# uMultimeter_PWR_Sch.net
KiCad netlist of a schematic drawn in Altium Designer
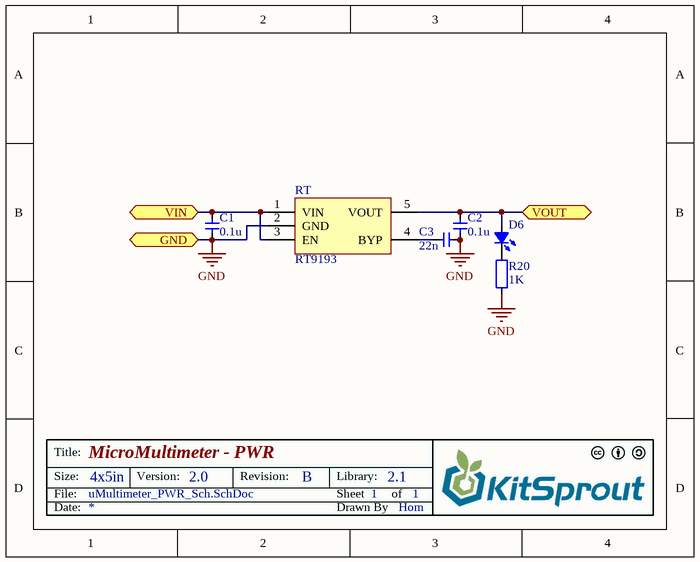
[diagram p0: uMultimeter_PWR_Sch.SchDoc]

(export (version "E")
  (design (tool "Eeschema 10.0.6"))
  (components
    (comp (ref "C1")
      (value "0.1u")
      (footprint "PCB_PassiveCap:CAP_0603")
      (description "Capacitor")
      (fields (field (name "Comment") "Cap_0603"))
      (libsource (lib "SCH_Passive") (part "Cap_0603"))
    )
    (comp (ref "C2")
      (value "0.1u")
      (footprint "PCB_PassiveCap:CAP_0603")
      (description "Capacitor")
      (fields (field (name "Comment") "Cap_0603"))
      (libsource (lib "SCH_Passive") (part "Cap_0603"))
    )
    (comp (ref "C3")
      (value "22n")
      (footprint "PCB_PassiveCap:CAP_0603")
      (description "Capacitor")
      (fields (field (name "Comment") "Cap_0603"))
      (libsource (lib "SCH_Passive") (part "Cap_0603"))
    )
    (comp (ref "D6")
      (value "LED_0805")
      (footprint "PCB_ActiveLED:LED_0805_ORANGE")
      (description "LED")
      (libsource (lib "SCH_Active") (part "LED_0805"))
    )
    (comp (ref "R20")
      (value "1K")
      (footprint "PCB_PassiveRes:RES_0603")
      (description "Resistor")
      (fields (field (name "Comment") "Res_0603"))
      (libsource (lib "SCH_Passive") (part "Res_0603"))
    )
    (comp (ref "RT")
      (value "RT9193")
      (footprint "PCB_IntegratedCircuit:SOT23-5")
      (description "Power")
      (libsource (lib "SCH_IntegratedCircuit") (part "SP6205"))
    )
  )
  (nets
    (net (code "1") (name "/VIN") (class "Default")
      (node (ref "C1") (pin "2") (pinfunction "2_2") (pintype "passive"))
      (node (ref "RT") (pin "1") (pinfunction "VIN_1") (pintype "passive"))
      (node (ref "RT") (pin "3") (pinfunction "EN_3") (pintype "power_in"))
    )
    (net (code "2") (name "/VOUT") (class "Default")
      (node (ref "C2") (pin "2") (pinfunction "2_2") (pintype "passive"))
      (node (ref "D6") (pin "1") (pinfunction "A_1") (pintype "passive"))
      (node (ref "RT") (pin "5") (pinfunction "VOUT_5") (pintype "passive"))
    )
    (net (code "3") (name "GND") (class "Default")
      (node (ref "C1") (pin "1") (pinfunction "1_1") (pintype "passive"))
      (node (ref "C2") (pin "1") (pinfunction "1_1") (pintype "passive"))
      (node (ref "C3") (pin "1") (pinfunction "1_1") (pintype "passive"))
      (node (ref "R20") (pin "2") (pinfunction "2_2") (pintype "passive"))
      (node (ref "RT") (pin "2") (pinfunction "GND_2") (pintype "passive"))
    )
    (net (code "4") (name "Net-(D6-K)") (class "Default")
      (node (ref "D6") (pin "2") (pinfunction "K_2") (pintype "passive"))
      (node (ref "R20") (pin "1") (pinfunction "1_1") (pintype "passive"))
    )
    (net (code "5") (name "Net-(RT-BYP)") (class "Default")
      (node (ref "C3") (pin "2") (pinfunction "2_2") (pintype "passive"))
      (node (ref "RT") (pin "4") (pinfunction "BYP_4") (pintype "passive"))
    )
  )
)
